# ESP32SSMB_V1_2.net
KiCad netlist of a schematic drawn in Altium Designer
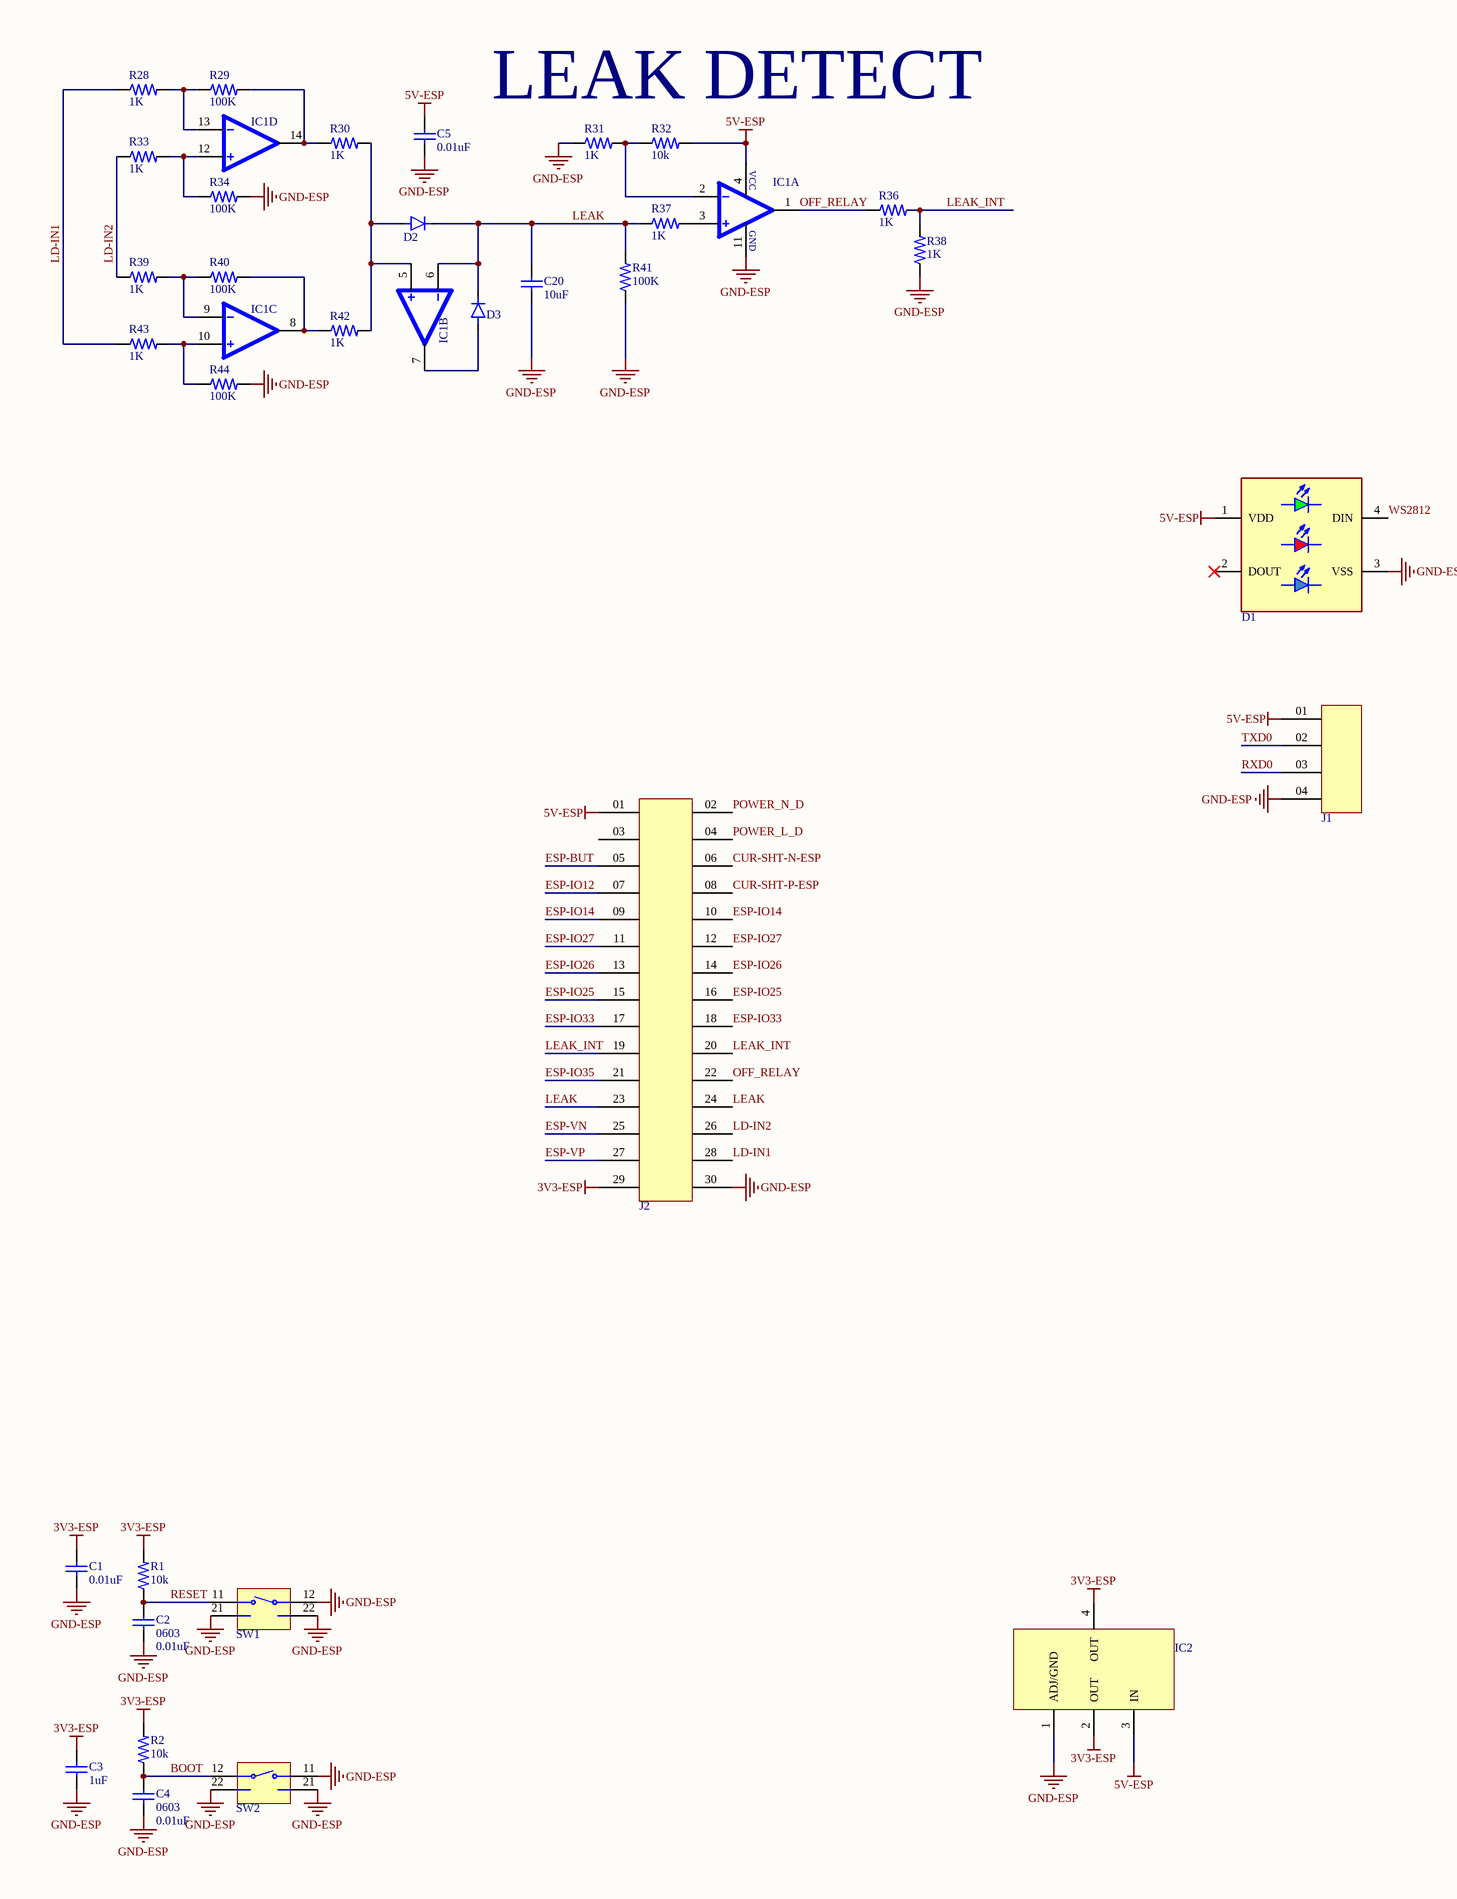
[diagram p0: ESP32SSMB V1.2 .SchDoc, left]
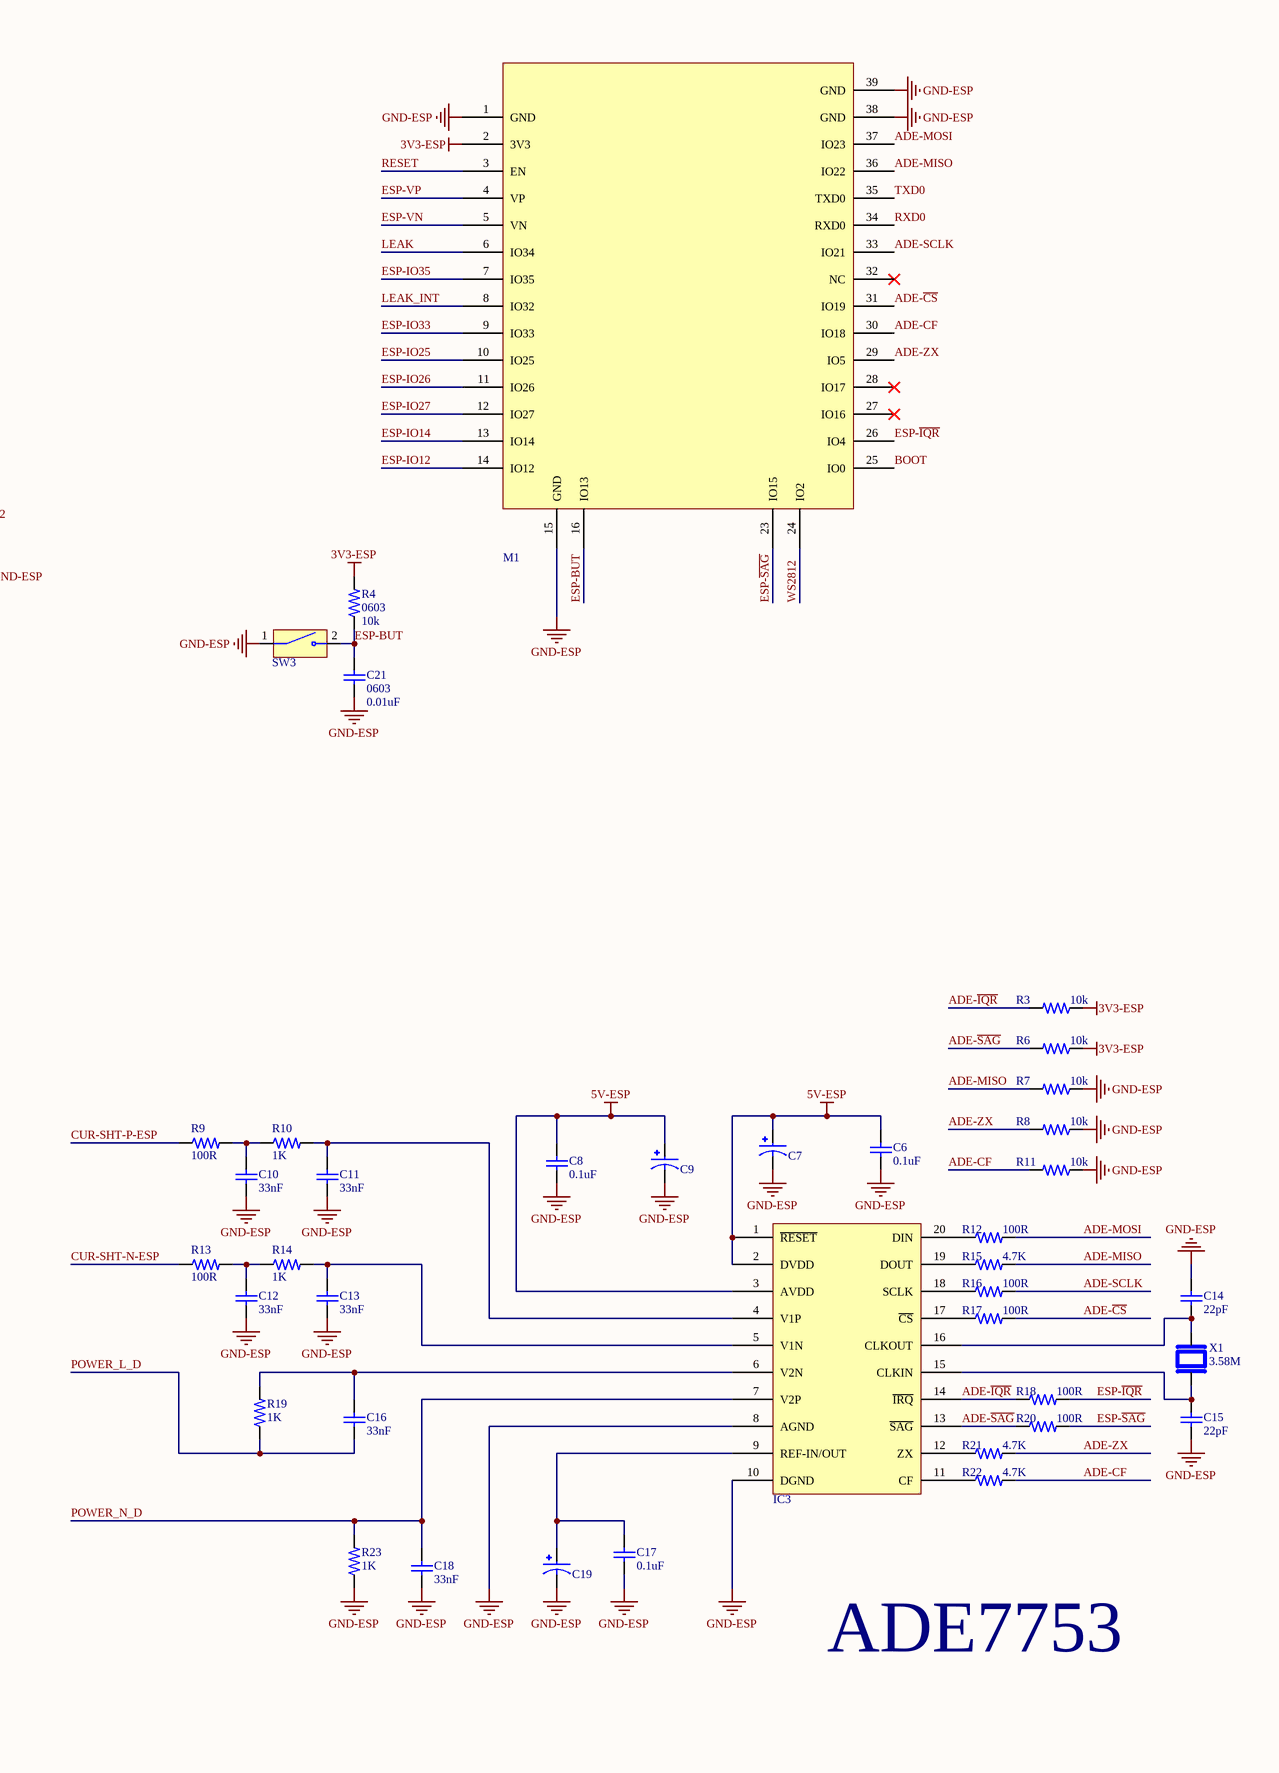
[diagram p1: ESP32SSMB V1.2 .SchDoc, right]

(export (version "E")
  (design (tool "Eeschema 10.0.6"))
  (components
    (comp (ref "C1")
      (value "0.01uF")
      (footprint "SMD-CAP-0603-YAGEO")
      (description "Multilayer Ceramic Capacitor, 0.1 uF, 10 V, ± 10%, X7R, 0603 [1608 Metric]")
      (fields
        (field (name "MANUFACTURER") "Yageo")
        (field (name "MANUFACTURER PART NUMBER") "CC0603KRX7R6BB104")
        (field (name "DESIGNER") "TVBac")
      )
      (libsource (lib "Capacitors") (part "CAP; 0.1uF; 10V; 0603; SMD; CC0603KRX7R6BB104"))
    )
    (comp (ref "C2")
      (value "0.01uF")
      (footprint "SMD-CAP-0603-YAGEO")
      (description "Multilayer Ceramic Capacitor, 0.01 uF, 16 V, ± 10%, X7R, 0603 [1608 Metric]")
      (fields
        (field (name "MANUFACTURER") "Yageo")
        (field (name "MANUFACTURER PART NUMBER") "CC0603KRX7R7BB103")
        (field (name "PACKAGE") "0603")
        (field (name "DESIGNER") "TVBac")
      )
      (libsource (lib "Capacitors") (part "CAP; 0.01uF; 16V; 0603; SMD; CC0603KRX7R7BB103"))
    )
    (comp (ref "C3")
      (value "1uF")
      (footprint "SMD-CAP-0603-YAGEO")
      (description "0603 1 uF 16 V ±10 % Tolerance X7R SMT Multilayer Ceramic Capacitor")
      (fields
        (field (name "MANUFACTURER") "Yageo")
        (field (name "MANUFACTURER PART NUMBER") "CC0603KRX7R7BB105")
        (field (name "DESIGNER") "TVBac")
      )
      (libsource (lib "Capacitors") (part "CAP; 1uF; 16V; 0603; SMD; CC0603KRX7R7BB105"))
    )
    (comp (ref "C4")
      (value "0.01uF")
      (footprint "SMD-CAP-0603-YAGEO")
      (description "Multilayer Ceramic Capacitor, 0.01 uF, 16 V, ± 10%, X7R, 0603 [1608 Metric]")
      (fields
        (field (name "MANUFACTURER") "Yageo")
        (field (name "MANUFACTURER PART NUMBER") "CC0603KRX7R7BB103")
        (field (name "PACKAGE") "0603")
        (field (name "DESIGNER") "TVBac")
      )
      (libsource (lib "Capacitors") (part "CAP; 0.01uF; 16V; 0603; SMD; CC0603KRX7R7BB103"))
    )
    (comp (ref "C5")
      (value "0.01uF")
      (footprint "SMD-CAP-0603-YAGEO")
      (description "Multilayer Ceramic Capacitor, 0.1 uF, 10 V, ± 10%, X7R, 0603 [1608 Metric]")
      (fields
        (field (name "MANUFACTURER") "Yageo")
        (field (name "MANUFACTURER PART NUMBER") "CC0603KRX7R6BB104")
        (field (name "DESIGNER") "TVBac")
      )
      (libsource (lib "Capacitors") (part "CAP; 0.1uF; 10V; 0603; SMD; CC0603KRX7R6BB104"))
    )
    (comp (ref "C6")
      (value "0.1uF")
      (footprint "SMD-CAP-0603-YAGEO")
      (description "0603 0.1 uF 16 V ±10 % Tolerance X7R SMT Multilayer Ceramic Capacitor")
      (fields
        (field (name "MANUFACTURER") "Yageo")
        (field (name "MANUFACTURER PART NUMBER") "CC0603KRX7R7BB104")
        (field (name "DESIGNER") "TVBac")
      )
      (libsource (lib "Capacitors") (part "CAP; 0.1uF; 16V; 0603; SMD; CC0603KRX7R7BB104"))
    )
    (comp (ref "C7")
      (value "10 µF Molded Tantalum Capacitors 10 V 1206 (3216 Metric) 3.8Ohm")
      (footprint "SMD-CAP-TAN-1206-KEMET")
      (description "Capacitor, Tantalum, Solid, Polarized, 10 V, 10 Uf, Surface Mount, 1206, Lead Free")
      (fields
        (field (name "MANUFACTURER") "KEMET")
        (field (name "MANUFACTURER PART NUMBER") "T491A106M010AT")
        (field (name "DESIGNER") "TVBac")
      )
      (libsource (lib "Capacitors") (part "CAP; CAP_TAN; 10uF; 10V; T491A106M010AT"))
    )
    (comp (ref "C8")
      (value "0.1uF")
      (footprint "SMD-CAP-0603-YAGEO")
      (description "0603 0.1 uF 16 V ±10 % Tolerance X7R SMT Multilayer Ceramic Capacitor")
      (fields
        (field (name "MANUFACTURER") "Yageo")
        (field (name "MANUFACTURER PART NUMBER") "CC0603KRX7R7BB104")
        (field (name "DESIGNER") "TVBac")
      )
      (libsource (lib "Capacitors") (part "CAP; 0.1uF; 16V; 0603; SMD; CC0603KRX7R7BB104"))
    )
    (comp (ref "C9")
      (value "10 µF Molded Tantalum Capacitors 10 V 1206 (3216 Metric) 3.8Ohm")
      (footprint "SMD-CAP-TAN-1206-KEMET")
      (description "Capacitor, Tantalum, Solid, Polarized, 10 V, 10 Uf, Surface Mount, 1206, Lead Free")
      (fields
        (field (name "MANUFACTURER") "KEMET")
        (field (name "MANUFACTURER PART NUMBER") "T491A106M010AT")
        (field (name "DESIGNER") "TVBac")
      )
      (libsource (lib "Capacitors") (part "CAP; CAP_TAN; 10uF; 10V; T491A106M010AT"))
    )
    (comp (ref "C10")
      (value "33nF")
      (footprint "SMD-CAP-0603-KEMET")
      (description "Multilayer Ceramic Capacitors MLCC - SMD/SMT 16V 0.033uF X7R 0603 5%")
      (fields
        (field (name "MANUFACTURER") "KEMET")
        (field (name "MANUFACTURER PART NUMBER") "C0603C333J4REC7411")
        (field (name "DESIGNER") "TVBac")
      )
      (libsource (lib "Capacitors") (part "CAP; 0.033uF; 33nF; 0603; 16V; C0603C333J4REC7411"))
    )
    (comp (ref "C11")
      (value "33nF")
      (footprint "SMD-CAP-0603-KEMET")
      (description "Multilayer Ceramic Capacitors MLCC - SMD/SMT 16V 0.033uF X7R 0603 5%")
      (fields
        (field (name "MANUFACTURER") "KEMET")
        (field (name "MANUFACTURER PART NUMBER") "C0603C333J4REC7411")
        (field (name "DESIGNER") "TVBac")
      )
      (libsource (lib "Capacitors") (part "CAP; 0.033uF; 33nF; 0603; 16V; C0603C333J4REC7411"))
    )
    (comp (ref "C12")
      (value "33nF")
      (footprint "SMD-CAP-0603-KEMET")
      (description "Multilayer Ceramic Capacitors MLCC - SMD/SMT 16V 0.033uF X7R 0603 5%")
      (fields
        (field (name "MANUFACTURER") "KEMET")
        (field (name "MANUFACTURER PART NUMBER") "C0603C333J4REC7411")
        (field (name "DESIGNER") "TVBac")
      )
      (libsource (lib "Capacitors") (part "CAP; 0.033uF; 33nF; 0603; 16V; C0603C333J4REC7411"))
    )
    (comp (ref "C13")
      (value "33nF")
      (footprint "SMD-CAP-0603-KEMET")
      (description "Multilayer Ceramic Capacitors MLCC - SMD/SMT 16V 0.033uF X7R 0603 5%")
      (fields
        (field (name "MANUFACTURER") "KEMET")
        (field (name "MANUFACTURER PART NUMBER") "C0603C333J4REC7411")
        (field (name "DESIGNER") "TVBac")
      )
      (libsource (lib "Capacitors") (part "CAP; 0.033uF; 33nF; 0603; 16V; C0603C333J4REC7411"))
    )
    (comp (ref "C14")
      (value "22pF")
      (footprint "SMD-CAP-0603-YAGEO")
      (description "Multilayer Ceramic Capacitor, 22 pF, 50 V, ï¿½ 1%, C0G (NP0), 0603 [1608 Metric]")
      (fields
        (field (name "MANUFACTURER") "Yageo")
        (field (name "MANUFACTURER PART NUMBER") "CC0603FRNPO9BN220")
        (field (name "DESIGNER") "TVBac")
      )
      (libsource (lib "Capacitors") (part "CAP; 22pF; 50V; SMD; CC0603FRNPO9BN220"))
    )
    (comp (ref "C15")
      (value "22pF")
      (footprint "SMD-CAP-0603-YAGEO")
      (description "Multilayer Ceramic Capacitor, 22 pF, 50 V, ï¿½ 1%, C0G (NP0), 0603 [1608 Metric]")
      (fields
        (field (name "MANUFACTURER") "Yageo")
        (field (name "MANUFACTURER PART NUMBER") "CC0603FRNPO9BN220")
        (field (name "DESIGNER") "TVBac")
      )
      (libsource (lib "Capacitors") (part "CAP; 22pF; 50V; SMD; CC0603FRNPO9BN220"))
    )
    (comp (ref "C16")
      (value "33nF")
      (footprint "SMD-CAP-0603-KEMET")
      (description "Multilayer Ceramic Capacitors MLCC - SMD/SMT 16V 0.033uF X7R 0603 5%")
      (fields
        (field (name "MANUFACTURER") "KEMET")
        (field (name "MANUFACTURER PART NUMBER") "C0603C333J4REC7411")
        (field (name "DESIGNER") "TVBac")
      )
      (libsource (lib "Capacitors") (part "CAP; 0.033uF; 33nF; 0603; 16V; C0603C333J4REC7411"))
    )
    (comp (ref "C17")
      (value "0.1uF")
      (footprint "SMD-CAP-0603-YAGEO")
      (description "0603 0.1 uF 16 V ±10 % Tolerance X7R SMT Multilayer Ceramic Capacitor")
      (fields
        (field (name "MANUFACTURER") "Yageo")
        (field (name "MANUFACTURER PART NUMBER") "CC0603KRX7R7BB104")
        (field (name "DESIGNER") "TVBac")
      )
      (libsource (lib "Capacitors") (part "CAP; 0.1uF; 16V; 0603; SMD; CC0603KRX7R7BB104"))
    )
    (comp (ref "C18")
      (value "33nF")
      (footprint "SMD-CAP-0603-KEMET")
      (description "Multilayer Ceramic Capacitors MLCC - SMD/SMT 16V 0.033uF X7R 0603 5%")
      (fields
        (field (name "MANUFACTURER") "KEMET")
        (field (name "MANUFACTURER PART NUMBER") "C0603C333J4REC7411")
        (field (name "DESIGNER") "TVBac")
      )
      (libsource (lib "Capacitors") (part "CAP; 0.033uF; 33nF; 0603; 16V; C0603C333J4REC7411"))
    )
    (comp (ref "C19")
      (value "10 µF Molded Tantalum Capacitors 10 V 1206 (3216 Metric) 3.8Ohm")
      (footprint "SMD-CAP-TAN-1206-KEMET")
      (description "Capacitor, Tantalum, Solid, Polarized, 10 V, 10 Uf, Surface Mount, 1206, Lead Free")
      (fields
        (field (name "MANUFACTURER") "KEMET")
        (field (name "MANUFACTURER PART NUMBER") "T491A106M010AT")
        (field (name "DESIGNER") "TVBac")
      )
      (libsource (lib "Capacitors") (part "CAP; CAP_TAN; 10uF; 10V; T491A106M010AT"))
    )
    (comp (ref "C20")
      (value "10uF")
      (footprint "SMD-CAP-0805-KEMET")
      (description "Multilayer Ceramic Capacitor, 10 uF, 6.3 V, ï¿½ 10%, X5R, 0805 [2012 Metric]")
      (fields
        (field (name "MANUFACTURER") "KEMET")
        (field (name "MANUFACTURER PART NUMBER") "C0805C106K9PACTU")
        (field (name "DESIGNER") "TVBac")
      )
      (libsource (lib "Capacitors") (part "CAP; 10uF; 10V; 0805; C0805C106K9PACTU"))
    )
    (comp (ref "C21")
      (value "0.01uF")
      (footprint "SMD-CAP-0603-YAGEO")
      (description "Multilayer Ceramic Capacitor, 0.01 uF, 16 V, ± 10%, X7R, 0603 [1608 Metric]")
      (fields
        (field (name "MANUFACTURER") "Yageo")
        (field (name "MANUFACTURER PART NUMBER") "CC0603KRX7R7BB103")
        (field (name "PACKAGE") "0603")
        (field (name "DESIGNER") "TVBac")
      )
      (libsource (lib "Capacitors") (part "CAP; 0.01uF; 16V; 0603; SMD; CC0603KRX7R7BB103"))
    )
    (comp (ref "D1")
      (value "Addressable Lighting - LED Serial NRZ (Shift Register) Red, Green, Blue (RGB) 5.00mm L x 5.00mm W")
      (footprint "SMD-LxW-5.0x5.0-WS2812-4PIN")
      (description "Address Led Red/grn/blue")
      (fields
        (field (name "MANUFACTURER") "SparkFun")
        (field (name "MANUFACTURER PART NUMBER") "COM-16347")
        (field (name "DESIGNER") "TVBac")
      )
      (libsource (lib "LED") (part "LED; RGB; WS2812; COM-16347"))
    )
    (comp (ref "D2")
      (value "Diode 1000 V 1A Surface Mount SOD-123FL")
      (footprint "SOD-123FL-SMCDS")
      (description "Diode Gen Purp 1KV 1A SOD123FL")
      (fields
        (field (name "MANUFACTURER") "Sangdest Microelectronics")
        (field (name "MANUFACTURER PART NUMBER") "1N4007FL")
        (field (name "DESIGNER") "TVBac")
      )
      (libsource (lib "Diode") (part "DIODE; SMD; 1N4007FLN4007;"))
    )
    (comp (ref "D3")
      (value "Diode 1000 V 1A Surface Mount SOD-123FL")
      (footprint "SOD-123FL-SMCDS")
      (description "Diode Gen Purp 1KV 1A SOD123FL")
      (fields
        (field (name "MANUFACTURER") "Sangdest Microelectronics")
        (field (name "MANUFACTURER PART NUMBER") "1N4007FL")
        (field (name "DESIGNER") "TVBac")
      )
      (libsource (lib "Diode") (part "DIODE; SMD; 1N4007FLN4007;"))
    )
    (comp (ref "IC1")
      (value "General Purpose Amplifier 4 Circuit 14-SOIC")
      (footprint "SOIC-14")
      (description "Quad 30-V 1.2-MHz operational amplifier 14-SOIC 0 to 70")
      (fields
        (field (name "MANUFACTURER") "Texas Instruments")
        (field (name "MANUFACTURER PART NUMBER") "LM324DR")
        (field (name "DESIGNER") "TVBac")
      )
      (libsource (lib "IC") (part "OPAM; SMD; LM324DR"))
    )
    (comp (ref "IC2")
      (value "Linear Voltage Regulator IC Positive Fixed 1 Output 1A SOT-223-3")
      (footprint "IC:SOT-223-3-DI")
      (description "Linear Voltage Regulator IC 1 Output 1A SOT-223")
      (fields
        (field (name "MF") "Diodes Inc.")
        (field (name "MP") "AZ1117EH-3.3TRG1")
        (field (name "DESIGNER") "TVBac")
      )
      (libsource (lib "IC") (part "LDO; 3V3; 1A; SMD; AZ1117EH-3.3TRG1"))
    )
    (comp (ref "IC3")
      (value "Single Phase Meter IC 20-SSOP")
      (footprint "SSOP-20-ADI")
      (description "Single Phase Multifunction Metering IC 20-Pin SSOP Tube")
      (fields
        (field (name "MANUFACTURER") "Analog Devices")
        (field (name "MANUFACTURER PART NUMBER") "ADE7753ARSZ")
        (field (name "DESIGNER") "TVBac")
      )
      (libsource (lib "IC") (part "ADE7753ARSZ"))
    )
    (comp (ref "J1")
      (value "Connector Header Through Hole 4 position 0.050\" (1.27mm)")
      (footprint "HEADER-1.27-4 - U3D")
      (description "Conn Unshrouded Header HDR 4 POS 1.27mm Solder ST Top Entry Thru-Hole Bulk")
      (fields
        (field (name "MANUFACTURER") "Samtec")
        (field (name "MANUFACTURER PART NUMBER") "TMS-104-02-G-S")
        (field (name "DESIGNER") "TVBac")
      )
      (libsource (lib "Socket") (part "HEADER; 4PIN; 1.27; VER; TMS-104-02-G-S"))
    )
    (comp (ref "J2")
      (value "HEADER; 15x2PIN; 2.54; HOR;")
      (footprint "HEADER-2.54-15x2-HOR")
      (fields (field (name "DESIGNER") "TVBac"))
      (libsource (lib "Socket") (part "HEADER; 15x2PIN; 2.54; HOR;"))
    )
    (comp (ref "M1")
      (value "Bluetooth, WiFi 802.11b/g/n, Bluetooth v4.2 +EDR, Class 1, 2 and 3 Transceiver Module 2.4GHz ~ 2.5GHz Integrated, Trace Surface Mount")
      (footprint "MODULE-ESP32-WROVER - WROOM")
      (description "Rf Txrx Module Bt Trace Ant SMD")
      (fields
        (field (name "MANUFACTURER") "Espressif Systems")
        (field (name "MANUFACTURER PART NUMBER") "ESP32-WROOM-32E-H4")
        (field (name "DESIGNER") "TVBac")
      )
      (libsource (lib "Modules") (part "ESP32-WROOM-WROVE-32E-H4; SMD;"))
    )
    (comp (ref "R1")
      (value "10k")
      (footprint "SMD-RES-0603-SEI")
      (description "SMD Chip Resistor, 10 kOhm, ± 1%, 250 mW, 0603 [1608 Metric], Thick Film, Anti-Surge")
      (fields
        (field (name "MANUFACTURER") "Rohm")
        (field (name "MANUFACTURER PART NUMBER") "ESR03EZPF1002")
        (field (name "DESIGNER") "TVBac")
      )
      (libsource (lib "Smartsocket") (part "RES; 10K; 0603; SMD; ESR03EZPF1002"))
    )
    (comp (ref "R2")
      (value "10k")
      (footprint "SMD-RES-0603-SEI")
      (description "SMD Chip Resistor, 10 kOhm, ± 1%, 250 mW, 0603 [1608 Metric], Thick Film, Anti-Surge")
      (fields
        (field (name "MANUFACTURER") "Rohm")
        (field (name "MANUFACTURER PART NUMBER") "ESR03EZPF1002")
        (field (name "DESIGNER") "TVBac")
      )
      (libsource (lib "Smartsocket") (part "RES; 10K; 0603; SMD; ESR03EZPF1002"))
    )
    (comp (ref "R3")
      (value "10k")
      (footprint "SMD-RES-0603-SEI")
      (description "SMD Chip Resistor, 10 kOhm, ± 1%, 250 mW, 0603 [1608 Metric], Thick Film, Anti-Surge")
      (fields
        (field (name "MANUFACTURER") "Rohm")
        (field (name "MANUFACTURER PART NUMBER") "ESR03EZPF1002")
        (field (name "DESIGNER") "TVBac")
      )
      (libsource (lib "Resistors") (part "RES; 10K; 0603; SMD; ESR03EZPF1002"))
    )
    (comp (ref "R4")
      (value "10k")
      (footprint "SMD-RES-0603-SEI")
      (description "SMD Chip Resistor, 10 kOhm, ± 1%, 250 mW, 0603 [1608 Metric], Thick Film, Anti-Surge")
      (fields
        (field (name "MANUFACTURER") "Rohm")
        (field (name "MANUFACTURER PART NUMBER") "ESR03EZPF1002")
        (field (name "PACKAGE") "0603")
        (field (name "DESIGNER") "TVBac")
      )
      (libsource (lib "Resistors") (part "RES; 10K; 0603; SMD; ESR03EZPF1002"))
    )
    (comp (ref "R6")
      (value "10k")
      (footprint "SMD-RES-0603-SEI")
      (description "SMD Chip Resistor, 10 kOhm, ± 1%, 250 mW, 0603 [1608 Metric], Thick Film, Anti-Surge")
      (fields
        (field (name "MANUFACTURER") "Rohm")
        (field (name "MANUFACTURER PART NUMBER") "ESR03EZPF1002")
        (field (name "DESIGNER") "TVBac")
      )
      (libsource (lib "Resistors") (part "RES; 10K; 0603; SMD; ESR03EZPF1002"))
    )
    (comp (ref "R7")
      (value "10k")
      (footprint "SMD-RES-0603-SEI")
      (description "SMD Chip Resistor, 10 kOhm, ± 1%, 250 mW, 0603 [1608 Metric], Thick Film, Anti-Surge")
      (fields
        (field (name "MANUFACTURER") "Rohm")
        (field (name "MANUFACTURER PART NUMBER") "ESR03EZPF1002")
        (field (name "DESIGNER") "TVBac")
      )
      (libsource (lib "Resistors") (part "RES; 10K; 0603; SMD; ESR03EZPF1002"))
    )
    (comp (ref "R8")
      (value "10k")
      (footprint "SMD-RES-0603-SEI")
      (description "SMD Chip Resistor, 10 kOhm, ± 1%, 250 mW, 0603 [1608 Metric], Thick Film, Anti-Surge")
      (fields
        (field (name "MANUFACTURER") "Rohm")
        (field (name "MANUFACTURER PART NUMBER") "ESR03EZPF1002")
        (field (name "DESIGNER") "TVBac")
      )
      (libsource (lib "Resistors") (part "RES; 10K; 0603; SMD; ESR03EZPF1002"))
    )
    (comp (ref "R9")
      (value "100R")
      (footprint "SMD-RES-0603-RS")
      (description "Res Thick Film 0603 100 Ohm 1% 0.1W(1/10W) ±100ppm/C Pad SMD T/R Automotive AEC-Q200")
      (fields
        (field (name "MANUFACTURER") "Rohm")
        (field (name "MANUFACTURER PART NUMBER") "KTR03EZPF1000")
        (field (name "DESIGNER") "TVBac")
      )
      (libsource (lib "Resistors") (part "RES; 100R; 0603; SMD; KTR03EZPF1000"))
    )
    (comp (ref "R10")
      (value "1K")
      (footprint "SMD-RES-0603-SEI")
      (description "SMD Chip Resistor, 1 kOhm, ± 1%, 250 mW, 0603 [1608 Metric], Thick Film, Anti-Surge")
      (fields
        (field (name "MANUFACTURER") "Rohm")
        (field (name "MANUFACTURER PART NUMBER") "ESR03EZPF1001")
        (field (name "DESIGNER") "TVBac")
      )
      (libsource (lib "Resistors") (part "RES; 1K; 0603; SMD; ESR03EZPF1001"))
    )
    (comp (ref "R11")
      (value "10k")
      (footprint "SMD-RES-0603-SEI")
      (description "SMD Chip Resistor, 10 kOhm, ± 1%, 250 mW, 0603 [1608 Metric], Thick Film, Anti-Surge")
      (fields
        (field (name "MANUFACTURER") "Rohm")
        (field (name "MANUFACTURER PART NUMBER") "ESR03EZPF1002")
        (field (name "DESIGNER") "TVBac")
      )
      (libsource (lib "Resistors") (part "RES; 10K; 0603; SMD; ESR03EZPF1002"))
    )
    (comp (ref "R12")
      (value "100R")
      (footprint "SMD-RES-0603-RS")
      (description "Res Thick Film 0603 100 Ohm 1% 0.1W(1/10W) ±100ppm/C Pad SMD T/R Automotive AEC-Q200")
      (fields
        (field (name "MANUFACTURER") "Rohm")
        (field (name "MANUFACTURER PART NUMBER") "KTR03EZPF1000")
        (field (name "DESIGNER") "TVBac")
      )
      (libsource (lib "Resistors") (part "RES; 100R; 0603; SMD; KTR03EZPF1000"))
    )
    (comp (ref "R13")
      (value "100R")
      (footprint "SMD-RES-0603-RS")
      (description "Res Thick Film 0603 100 Ohm 1% 0.1W(1/10W) ±100ppm/C Pad SMD T/R Automotive AEC-Q200")
      (fields
        (field (name "MANUFACTURER") "Rohm")
        (field (name "MANUFACTURER PART NUMBER") "KTR03EZPF1000")
        (field (name "DESIGNER") "TVBac")
      )
      (libsource (lib "Resistors") (part "RES; 100R; 0603; SMD; KTR03EZPF1000"))
    )
    (comp (ref "R14")
      (value "1K")
      (footprint "SMD-RES-0603-SEI")
      (description "SMD Chip Resistor, 1 kOhm, ± 1%, 250 mW, 0603 [1608 Metric], Thick Film, Anti-Surge")
      (fields
        (field (name "MANUFACTURER") "Rohm")
        (field (name "MANUFACTURER PART NUMBER") "ESR03EZPF1001")
        (field (name "DESIGNER") "TVBac")
      )
      (libsource (lib "Resistors") (part "RES; 1K; 0603; SMD; ESR03EZPF1001"))
    )
    (comp (ref "R15")
      (value "4.7K")
      (footprint "SMD-RES-0603-RS")
      (description "Res Anti-Sulfured Thick Film 0603 4.7k Ohm 1% 1/10W ±100ppm/°C Molded Paper T/R")
      (fields
        (field (name "MANUFACTURER") "Rohm")
        (field (name "MANUFACTURER PART NUMBER") "SFR03EZPF4701")
        (field (name "DESIGNER") "TVBac")
      )
      (libsource (lib "Resistors") (part "RES; 4.7K; 0603; SMD; SFR03EZPF4701"))
    )
    (comp (ref "R16")
      (value "100R")
      (footprint "SMD-RES-0603-RS")
      (description "Res Thick Film 0603 100 Ohm 1% 0.1W(1/10W) ±100ppm/C Pad SMD T/R Automotive AEC-Q200")
      (fields
        (field (name "MANUFACTURER") "Rohm")
        (field (name "MANUFACTURER PART NUMBER") "KTR03EZPF1000")
        (field (name "DESIGNER") "TVBac")
      )
      (libsource (lib "Resistors") (part "RES; 100R; 0603; SMD; KTR03EZPF1000"))
    )
    (comp (ref "R17")
      (value "100R")
      (footprint "SMD-RES-0603-RS")
      (description "Res Thick Film 0603 100 Ohm 1% 0.1W(1/10W) ±100ppm/C Pad SMD T/R Automotive AEC-Q200")
      (fields
        (field (name "MANUFACTURER") "Rohm")
        (field (name "MANUFACTURER PART NUMBER") "KTR03EZPF1000")
        (field (name "DESIGNER") "TVBac")
      )
      (libsource (lib "Resistors") (part "RES; 100R; 0603; SMD; KTR03EZPF1000"))
    )
    (comp (ref "R18")
      (value "100R")
      (footprint "SMD-RES-0603-RS")
      (description "Res Thick Film 0603 100 Ohm 1% 0.1W(1/10W) ±100ppm/C Pad SMD T/R Automotive AEC-Q200")
      (fields
        (field (name "MANUFACTURER") "Rohm")
        (field (name "MANUFACTURER PART NUMBER") "KTR03EZPF1000")
        (field (name "DESIGNER") "TVBac")
      )
      (libsource (lib "Resistors") (part "RES; 100R; 0603; SMD; KTR03EZPF1000"))
    )
    (comp (ref "R19")
      (value "1K")
      (footprint "SMD-RES-0603-SEI")
      (description "SMD Chip Resistor, 1 kOhm, ± 1%, 250 mW, 0603 [1608 Metric], Thick Film, Anti-Surge")
      (fields
        (field (name "MANUFACTURER") "Rohm")
        (field (name "MANUFACTURER PART NUMBER") "ESR03EZPF1001")
        (field (name "DESIGNER") "TVBac")
      )
      (libsource (lib "Resistors") (part "RES; 1K; 0603; SMD; ESR03EZPF1001"))
    )
    (comp (ref "R20")
      (value "100R")
      (footprint "SMD-RES-0603-RS")
      (description "Res Thick Film 0603 100 Ohm 1% 0.1W(1/10W) ±100ppm/C Pad SMD T/R Automotive AEC-Q200")
      (fields
        (field (name "MANUFACTURER") "Rohm")
        (field (name "MANUFACTURER PART NUMBER") "KTR03EZPF1000")
        (field (name "DESIGNER") "TVBac")
      )
      (libsource (lib "Resistors") (part "RES; 100R; 0603; SMD; KTR03EZPF1000"))
    )
    (comp (ref "R21")
      (value "4.7K")
      (footprint "SMD-RES-0603-RS")
      (description "Res Anti-Sulfured Thick Film 0603 4.7k Ohm 1% 1/10W ±100ppm/°C Molded Paper T/R")
      (fields
        (field (name "MANUFACTURER") "Rohm")
        (field (name "MANUFACTURER PART NUMBER") "SFR03EZPF4701")
        (field (name "DESIGNER") "TVBac")
      )
      (libsource (lib "Resistors") (part "RES; 4.7K; 0603; SMD; SFR03EZPF4701"))
    )
    (comp (ref "R22")
      (value "4.7K")
      (footprint "SMD-RES-0603-RS")
      (description "Res Anti-Sulfured Thick Film 0603 4.7k Ohm 1% 1/10W ±100ppm/°C Molded Paper T/R")
      (fields
        (field (name "MANUFACTURER") "Rohm")
        (field (name "MANUFACTURER PART NUMBER") "SFR03EZPF4701")
        (field (name "DESIGNER") "TVBac")
      )
      (libsource (lib "Resistors") (part "RES; 4.7K; 0603; SMD; SFR03EZPF4701"))
    )
    (comp (ref "R23")
      (value "1K")
      (footprint "SMD-RES-0603-SEI")
      (description "SMD Chip Resistor, 1 kOhm, ± 1%, 250 mW, 0603 [1608 Metric], Thick Film, Anti-Surge")
      (fields
        (field (name "MANUFACTURER") "Rohm")
        (field (name "MANUFACTURER PART NUMBER") "ESR03EZPF1001")
        (field (name "DESIGNER") "TVBac")
      )
      (libsource (lib "Resistors") (part "RES; 1K; 0603; SMD; ESR03EZPF1001"))
    )
    (comp (ref "R28")
      (value "1K")
      (footprint "SMD-RES-0603-SEI")
      (description "SMD Chip Resistor, 1 kOhm, ± 1%, 250 mW, 0603 [1608 Metric], Thick Film, Anti-Surge")
      (fields
        (field (name "MANUFACTURER") "Rohm")
        (field (name "MANUFACTURER PART NUMBER") "ESR03EZPF1001")
        (field (name "DESIGNER") "TVBac")
      )
      (libsource (lib "Resistors") (part "RES; 1K; 0603; SMD; ESR03EZPF1001"))
    )
    (comp (ref "R29")
      (value "100K")
      (footprint "SMD-RES-0603-SEI")
      (description "Res Thick Film 0603 100K Ohm 5% 0.25W(1/4W) ±200ppm/C Pad SMD Automotive T/R")
      (fields
        (field (name "MANUFACTURER") "Rohm")
        (field (name "MANUFACTURER PART NUMBER") "ESR03EZPJ104")
        (field (name "DESIGNER") "TVBac")
      )
      (libsource (lib "Resistors") (part "RES; 100K; 0603; SMD; ESR03EZPJ104"))
    )
    (comp (ref "R30")
      (value "1K")
      (footprint "SMD-RES-0603-SEI")
      (description "SMD Chip Resistor, 1 kOhm, ± 1%, 250 mW, 0603 [1608 Metric], Thick Film, Anti-Surge")
      (fields
        (field (name "MANUFACTURER") "Rohm")
        (field (name "MANUFACTURER PART NUMBER") "ESR03EZPF1001")
        (field (name "DESIGNER") "TVBac")
      )
      (libsource (lib "Resistors") (part "RES; 1K; 0603; SMD; ESR03EZPF1001"))
    )
    (comp (ref "R31")
      (value "1K")
      (footprint "SMD-RES-0603-SEI")
      (description "SMD Chip Resistor, 1 kOhm, ± 1%, 250 mW, 0603 [1608 Metric], Thick Film, Anti-Surge")
      (fields
        (field (name "MANUFACTURER") "Rohm")
        (field (name "MANUFACTURER PART NUMBER") "ESR03EZPF1001")
        (field (name "DESIGNER") "TVBac")
      )
      (libsource (lib "Resistors") (part "RES; 1K; 0603; SMD; ESR03EZPF1001"))
    )
    (comp (ref "R32")
      (value "10k")
      (footprint "SMD-RES-0603-SEI")
      (description "SMD Chip Resistor, 10 kOhm, ± 1%, 250 mW, 0603 [1608 Metric], Thick Film, Anti-Surge")
      (fields
        (field (name "MANUFACTURER") "Rohm")
        (field (name "MANUFACTURER PART NUMBER") "ESR03EZPF1002")
        (field (name "DESIGNER") "TVBac")
      )
      (libsource (lib "Resistors") (part "RES; 10K; 0603; SMD; ESR03EZPF1002"))
    )
    (comp (ref "R33")
      (value "1K")
      (footprint "SMD-RES-0603-SEI")
      (description "SMD Chip Resistor, 1 kOhm, ± 1%, 250 mW, 0603 [1608 Metric], Thick Film, Anti-Surge")
      (fields
        (field (name "MANUFACTURER") "Rohm")
        (field (name "MANUFACTURER PART NUMBER") "ESR03EZPF1001")
        (field (name "DESIGNER") "TVBac")
      )
      (libsource (lib "Resistors") (part "RES; 1K; 0603; SMD; ESR03EZPF1001"))
    )
    (comp (ref "R34")
      (value "100K")
      (footprint "SMD-RES-0603-SEI")
      (description "Res Thick Film 0603 100K Ohm 5% 0.25W(1/4W) ±200ppm/C Pad SMD Automotive T/R")
      (fields
        (field (name "MANUFACTURER") "Rohm")
        (field (name "MANUFACTURER PART NUMBER") "ESR03EZPJ104")
        (field (name "DESIGNER") "TVBac")
      )
      (libsource (lib "Resistors") (part "RES; 100K; 0603; SMD; ESR03EZPJ104"))
    )
    (comp (ref "R36")
      (value "1K")
      (footprint "SMD-RES-0603-SEI")
      (description "SMD Chip Resistor, 1 kOhm, ± 1%, 250 mW, 0603 [1608 Metric], Thick Film, Anti-Surge")
      (fields
        (field (name "MANUFACTURER") "Rohm")
        (field (name "MANUFACTURER PART NUMBER") "ESR03EZPF1001")
        (field (name "DESIGNER") "TVBac")
      )
      (libsource (lib "Resistors") (part "RES; 1K; 0603; SMD; ESR03EZPF1001"))
    )
    (comp (ref "R37")
      (value "1K")
      (footprint "SMD-RES-0603-SEI")
      (description "SMD Chip Resistor, 1 kOhm, ± 1%, 250 mW, 0603 [1608 Metric], Thick Film, Anti-Surge")
      (fields
        (field (name "MANUFACTURER") "Rohm")
        (field (name "MANUFACTURER PART NUMBER") "ESR03EZPF1001")
        (field (name "DESIGNER") "TVBac")
      )
      (libsource (lib "Resistors") (part "RES; 1K; 0603; SMD; ESR03EZPF1001"))
    )
    (comp (ref "R38")
      (value "1K")
      (footprint "SMD-RES-0603-SEI")
      (description "SMD Chip Resistor, 1 kOhm, ± 1%, 250 mW, 0603 [1608 Metric], Thick Film, Anti-Surge")
      (fields
        (field (name "MANUFACTURER") "Rohm")
        (field (name "MANUFACTURER PART NUMBER") "ESR03EZPF1001")
        (field (name "DESIGNER") "TVBac")
      )
      (libsource (lib "Resistors") (part "RES; 1K; 0603; SMD; ESR03EZPF1001"))
    )
    (comp (ref "R39")
      (value "1K")
      (footprint "SMD-RES-0603-SEI")
      (description "SMD Chip Resistor, 1 kOhm, ± 1%, 250 mW, 0603 [1608 Metric], Thick Film, Anti-Surge")
      (fields
        (field (name "MANUFACTURER") "Rohm")
        (field (name "MANUFACTURER PART NUMBER") "ESR03EZPF1001")
        (field (name "DESIGNER") "TVBac")
      )
      (libsource (lib "Resistors") (part "RES; 1K; 0603; SMD; ESR03EZPF1001"))
    )
    (comp (ref "R40")
      (value "100K")
      (footprint "SMD-RES-0603-SEI")
      (description "Res Thick Film 0603 100K Ohm 5% 0.25W(1/4W) ±200ppm/C Pad SMD Automotive T/R")
      (fields
        (field (name "MANUFACTURER") "Rohm")
        (field (name "MANUFACTURER PART NUMBER") "ESR03EZPJ104")
        (field (name "DESIGNER") "TVBac")
      )
      (libsource (lib "Resistors") (part "RES; 100K; 0603; SMD; ESR03EZPJ104"))
    )
    (comp (ref "R41")
      (value "100K")
      (footprint "SMD-RES-0603-SEI")
      (description "Res Thick Film 0603 100K Ohm 5% 0.25W(1/4W) ±200ppm/C Pad SMD Automotive T/R")
      (fields
        (field (name "MANUFACTURER") "Rohm")
        (field (name "MANUFACTURER PART NUMBER") "ESR03EZPJ104")
        (field (name "DESIGNER") "TVBac")
      )
      (libsource (lib "Resistors") (part "RES; 100K; 0603; SMD; ESR03EZPJ104"))
    )
    (comp (ref "R42")
      (value "1K")
      (footprint "SMD-RES-0603-SEI")
      (description "SMD Chip Resistor, 1 kOhm, ± 1%, 250 mW, 0603 [1608 Metric], Thick Film, Anti-Surge")
      (fields
        (field (name "MANUFACTURER") "Rohm")
        (field (name "MANUFACTURER PART NUMBER") "ESR03EZPF1001")
        (field (name "DESIGNER") "TVBac")
      )
      (libsource (lib "Resistors") (part "RES; 1K; 0603; SMD; ESR03EZPF1001"))
    )
    (comp (ref "R43")
      (value "1K")
      (footprint "SMD-RES-0603-SEI")
      (description "SMD Chip Resistor, 1 kOhm, ± 1%, 250 mW, 0603 [1608 Metric], Thick Film, Anti-Surge")
      (fields
        (field (name "MANUFACTURER") "Rohm")
        (field (name "MANUFACTURER PART NUMBER") "ESR03EZPF1001")
        (field (name "DESIGNER") "TVBac")
      )
      (libsource (lib "Resistors") (part "RES; 1K; 0603; SMD; ESR03EZPF1001"))
    )
    (comp (ref "R44")
      (value "100K")
      (footprint "SMD-RES-0603-SEI")
      (description "Res Thick Film 0603 100K Ohm 5% 0.25W(1/4W) ±200ppm/C Pad SMD Automotive T/R")
      (fields
        (field (name "MANUFACTURER") "Rohm")
        (field (name "MANUFACTURER PART NUMBER") "ESR03EZPJ104")
        (field (name "DESIGNER") "TVBac")
      )
      (libsource (lib "Resistors") (part "RES; 100K; 0603; SMD; ESR03EZPJ104"))
    )
    (comp (ref "SW1")
      (value "https://www.digikey.com/en/products/detail/panasonic-electronic-components/EVQ-P7L01P/4429453")
      (footprint "SW-HxLxW-1.1x3.5x2.9-PEC")
      (description "Tactile Switch SPST-NO Side Actuated Surface Mount, Right Angle")
      (fields (field (name "MP") "EVQ-P7L01P") (field (name "MF") "Panasonic Electronic Components"))
      (libsource (lib "Button") (part "BUT; SW; SMD; EVQ-P7L01P"))
    )
    (comp (ref "SW2")
      (value "https://www.digikey.com/en/products/detail/panasonic-electronic-components/EVQ-P7L01P/4429453")
      (footprint "SW-HxLxW-1.1x3.5x2.9-PEC")
      (description "Tactile Switch SPST-NO Side Actuated Surface Mount, Right Angle")
      (fields (field (name "MP") "EVQ-P7L01P") (field (name "MF") "Panasonic Electronic Components"))
      (libsource (lib "") (part "BUT; SW; SMD; EVQ-P7L01P_1"))
    )
    (comp (ref "SW3")
      (value "Tactile Switch SPST-NO Top Actuated Surface Mount")
      (footprint "SW-HxLxW-5.0x6.0x3.5-C&K")
      (description "Switch Tactile N.O. SPST Rectangular Button J-Bend 0.05A 12VDC 1.77N SMD T/R")
      (fields
        (field (name "MANUFACTURER") "ITT C&K")
        (field (name "MANUFACTURER PART NUMBER") "PTS636SM50JSMTRLFS")
      )
      (libsource (lib "Button") (part "BUT; SW; SMD; PTS636SM50JSMTRLFS"))
    )
    (comp (ref "X1")
      (value "3.58M")
      (footprint "SMD-HC-49/US-ALLC")
      (description "Crystal 3.579545MHz ±20ppm (Tol) ±50ppm (Stability) 18pF FUND 180Ohm 2-Pin HC-49/US SMD T/R")
      (fields
        (field (name "MANUFACTURER") "Abracon")
        (field (name "MANUFACTURER PART NUMBER") "ABLS-3.579545MHZ-B2-T")
        (field (name "DESIGNER") "TVBac")
      )
      (libsource (lib "Oscillators") (part "OSC; 3.58M; 3.579545M; ABLS-3.579545MHZ-B2-T"))
    )
  )
  (nets
    (net (code "1") (name "/ADE-CF") (class "Default")
      (node (ref "M1") (pin "30") (pinfunction "IO18_30") (pintype "passive"))
      (node (ref "R11") (pin "2") (pinfunction "2_2") (pintype "passive"))
      (node (ref "R22") (pin "2") (pinfunction "2_2") (pintype "passive"))
    )
    (net (code "2") (name "/ADE-MISO") (class "Default")
      (node (ref "M1") (pin "36") (pinfunction "IO22_36") (pintype "passive"))
      (node (ref "R15") (pin "2") (pinfunction "2_2") (pintype "passive"))
      (node (ref "R7") (pin "2") (pinfunction "2_2") (pintype "passive"))
    )
    (net (code "3") (name "/ADE-MOSI") (class "Default")
      (node (ref "M1") (pin "37") (pinfunction "IO23_37") (pintype "passive"))
      (node (ref "R12") (pin "2") (pinfunction "2_2") (pintype "passive"))
    )
    (net (code "4") (name "/ADE-SCLK") (class "Default")
      (node (ref "M1") (pin "33") (pinfunction "IO21_33") (pintype "passive"))
      (node (ref "R16") (pin "2") (pinfunction "2_2") (pintype "passive"))
    )
    (net (code "5") (name "/ADE-ZX") (class "Default")
      (node (ref "M1") (pin "29") (pinfunction "IO5_29") (pintype "passive"))
      (node (ref "R21") (pin "2") (pinfunction "2_2") (pintype "passive"))
      (node (ref "R8") (pin "2") (pinfunction "2_2") (pintype "passive"))
    )
    (net (code "6") (name "/ADE-~{CS}") (class "Default")
      (node (ref "M1") (pin "31") (pinfunction "IO19_31") (pintype "passive"))
      (node (ref "R17") (pin "2") (pinfunction "2_2") (pintype "passive"))
    )
    (net (code "7") (name "/ADE-~{IQR}") (class "Default")
      (node (ref "IC3") (pin "14") (pinfunction "~{IRQ}_14") (pintype "passive"))
      (node (ref "R18") (pin "1") (pinfunction "1_1") (pintype "passive"))
      (node (ref "R3") (pin "2") (pinfunction "2_2") (pintype "passive"))
    )
    (net (code "8") (name "/ADE-~{SAG}") (class "Default")
      (node (ref "IC3") (pin "13") (pinfunction "~{SAG}_13") (pintype "passive"))
      (node (ref "R20") (pin "1") (pinfunction "1_1") (pintype "passive"))
      (node (ref "R6") (pin "2") (pinfunction "2_2") (pintype "passive"))
    )
    (net (code "9") (name "/BOOT") (class "Default")
      (node (ref "C4") (pin "2") (pinfunction "2_2") (pintype "passive"))
      (node (ref "M1") (pin "25") (pinfunction "IO0_25") (pintype "passive"))
      (node (ref "R2") (pin "1") (pinfunction "1_1") (pintype "passive"))
      (node (ref "SW2") (pin "12") (pinfunction "2_12") (pintype "passive"))
    )
    (net (code "10") (name "/CUR-SHT-N-ESP") (class "Default")
      (node (ref "J2") (pin "06") (pinfunction "06_06") (pintype "passive"))
      (node (ref "R13") (pin "1") (pinfunction "1_1") (pintype "passive"))
    )
    (net (code "11") (name "/CUR-SHT-P-ESP") (class "Default")
      (node (ref "J2") (pin "08") (pinfunction "08_08") (pintype "passive"))
      (node (ref "R9") (pin "1") (pinfunction "1_1") (pintype "passive"))
    )
    (net (code "12") (name "/ESP-BUT") (class "Default")
      (node (ref "C21") (pin "2") (pinfunction "2_2") (pintype "passive"))
      (node (ref "J2") (pin "05") (pinfunction "05_05") (pintype "passive"))
      (node (ref "M1") (pin "16") (pinfunction "IO13_16") (pintype "passive"))
      (node (ref "R4") (pin "1") (pinfunction "1_1") (pintype "passive"))
      (node (ref "SW3") (pin "2") (pinfunction "NO_2") (pintype "passive"))
    )
    (net (code "13") (name "/ESP-IO12") (class "Default")
      (node (ref "J2") (pin "07") (pinfunction "07_07") (pintype "passive"))
      (node (ref "M1") (pin "14") (pinfunction "IO12_14") (pintype "passive"))
    )
    (net (code "14") (name "/ESP-IO14") (class "Default")
      (node (ref "J2") (pin "09") (pinfunction "09_09") (pintype "passive"))
      (node (ref "J2") (pin "10") (pinfunction "10_10") (pintype "passive"))
      (node (ref "M1") (pin "13") (pinfunction "IO14_13") (pintype "passive"))
    )
    (net (code "15") (name "/ESP-IO25") (class "Default")
      (node (ref "J2") (pin "15") (pinfunction "15_15") (pintype "passive"))
      (node (ref "J2") (pin "16") (pinfunction "16_16") (pintype "passive"))
      (node (ref "M1") (pin "10") (pinfunction "IO25_10") (pintype "passive"))
    )
    (net (code "16") (name "/ESP-IO26") (class "Default")
      (node (ref "J2") (pin "13") (pinfunction "13_13") (pintype "passive"))
      (node (ref "J2") (pin "14") (pinfunction "14_14") (pintype "passive"))
      (node (ref "M1") (pin "11") (pinfunction "IO26_11") (pintype "passive"))
    )
    (net (code "17") (name "/ESP-IO27") (class "Default")
      (node (ref "J2") (pin "11") (pinfunction "11_11") (pintype "passive"))
      (node (ref "J2") (pin "12") (pinfunction "12_12") (pintype "passive"))
      (node (ref "M1") (pin "12") (pinfunction "IO27_12") (pintype "passive"))
    )
    (net (code "18") (name "/ESP-IO33") (class "Default")
      (node (ref "J2") (pin "17") (pinfunction "17_17") (pintype "passive"))
      (node (ref "J2") (pin "18") (pinfunction "18_18") (pintype "passive"))
      (node (ref "M1") (pin "9") (pinfunction "IO33_9") (pintype "passive"))
    )
    (net (code "19") (name "/ESP-IO35") (class "Default")
      (node (ref "J2") (pin "21") (pinfunction "21_21") (pintype "passive"))
      (node (ref "M1") (pin "7") (pinfunction "IO35_7") (pintype "passive"))
    )
    (net (code "20") (name "/ESP-VN") (class "Default")
      (node (ref "J2") (pin "25") (pinfunction "25_25") (pintype "passive"))
      (node (ref "M1") (pin "5") (pinfunction "VN_5") (pintype "passive"))
    )
    (net (code "21") (name "/ESP-VP") (class "Default")
      (node (ref "J2") (pin "27") (pinfunction "27_27") (pintype "passive"))
      (node (ref "M1") (pin "4") (pinfunction "VP_4") (pintype "passive"))
    )
    (net (code "22") (name "/ESP-~{IQR}") (class "Default")
      (node (ref "M1") (pin "26") (pinfunction "IO4_26") (pintype "passive"))
      (node (ref "R18") (pin "2") (pinfunction "2_2") (pintype "passive"))
    )
    (net (code "23") (name "/ESP-~{SAG}") (class "Default")
      (node (ref "M1") (pin "23") (pinfunction "IO15_23") (pintype "passive"))
      (node (ref "R20") (pin "2") (pinfunction "2_2") (pintype "passive"))
    )
    (net (code "24") (name "/LD-IN1") (class "Default")
      (node (ref "J2") (pin "28") (pinfunction "28_28") (pintype "passive"))
      (node (ref "R28") (pin "1") (pinfunction "1_1") (pintype "passive"))
      (node (ref "R43") (pin "1") (pinfunction "1_1") (pintype "passive"))
    )
    (net (code "25") (name "/LD-IN2") (class "Default")
      (node (ref "J2") (pin "26") (pinfunction "26_26") (pintype "passive"))
      (node (ref "R33") (pin "1") (pinfunction "1_1") (pintype "passive"))
      (node (ref "R39") (pin "1") (pinfunction "1_1") (pintype "passive"))
    )
    (net (code "26") (name "/LEAK") (class "Default")
      (node (ref "C20") (pin "2") (pinfunction "2_2") (pintype "passive"))
      (node (ref "D2") (pin "K") (pinfunction "K_K") (pintype "passive"))
      (node (ref "D3") (pin "K") (pinfunction "K_K") (pintype "passive"))
      (node (ref "IC1") (pin "6") (pinfunction "2IN-_6") (pintype "passive"))
      (node (ref "J2") (pin "23") (pinfunction "23_23") (pintype "passive"))
      (node (ref "J2") (pin "24") (pinfunction "24_24") (pintype "passive"))
      (node (ref "M1") (pin "6") (pinfunction "IO34_6") (pintype "passive"))
      (node (ref "R37") (pin "1") (pinfunction "1_1") (pintype "passive"))
      (node (ref "R41") (pin "2") (pinfunction "2_2") (pintype "passive"))
    )
    (net (code "27") (name "/LEAK_INT") (class "Default")
      (node (ref "J2") (pin "19") (pinfunction "19_19") (pintype "passive"))
      (node (ref "J2") (pin "20") (pinfunction "20_20") (pintype "passive"))
      (node (ref "M1") (pin "8") (pinfunction "IO32_8") (pintype "passive"))
      (node (ref "R36") (pin "2") (pinfunction "2_2") (pintype "passive"))
      (node (ref "R38") (pin "2") (pinfunction "2_2") (pintype "passive"))
    )
    (net (code "28") (name "/OFF_RELAY") (class "Default")
      (node (ref "IC1") (pin "1") (pinfunction "1OUT_1") (pintype "passive"))
      (node (ref "J2") (pin "22") (pinfunction "22_22") (pintype "passive"))
      (node (ref "R36") (pin "1") (pinfunction "1_1") (pintype "passive"))
    )
    (net (code "29") (name "/POWER_L_D") (class "Default")
      (node (ref "C16") (pin "1") (pinfunction "1_1") (pintype "passive"))
      (node (ref "J2") (pin "04") (pinfunction "04_04") (pintype "passive"))
      (node (ref "R19") (pin "1") (pinfunction "1_1") (pintype "passive"))
    )
    (net (code "30") (name "/POWER_N_D") (class "Default")
      (node (ref "C18") (pin "2") (pinfunction "2_2") (pintype "passive"))
      (node (ref "IC3") (pin "7") (pinfunction "V2P_7") (pintype "passive"))
      (node (ref "J2") (pin "02") (pinfunction "02_02") (pintype "passive"))
      (node (ref "R23") (pin "2") (pinfunction "2_2") (pintype "passive"))
    )
    (net (code "31") (name "/RESET") (class "Default")
      (node (ref "C2") (pin "2") (pinfunction "2_2") (pintype "passive"))
      (node (ref "M1") (pin "3") (pinfunction "EN_3") (pintype "passive"))
      (node (ref "R1") (pin "1") (pinfunction "1_1") (pintype "passive"))
      (node (ref "SW1") (pin "11") (pinfunction "1_11") (pintype "passive"))
    )
    (net (code "32") (name "/RXD0") (class "Default")
      (node (ref "J1") (pin "03") (pinfunction "2_03") (pintype "passive"))
      (node (ref "M1") (pin "34") (pinfunction "RXD0_34") (pintype "passive"))
    )
    (net (code "33") (name "/TXD0") (class "Default")
      (node (ref "J1") (pin "02") (pinfunction "2_02") (pintype "passive"))
      (node (ref "M1") (pin "35") (pinfunction "TXD0_35") (pintype "passive"))
    )
    (net (code "34") (name "/WS2812") (class "Default")
      (node (ref "D1") (pin "4") (pinfunction "DIN_4") (pintype "passive"))
      (node (ref "M1") (pin "24") (pinfunction "IO2_24") (pintype "passive"))
    )
    (net (code "35") (name "3V3-ESP") (class "Default")
      (node (ref "C1") (pin "2") (pinfunction "2_2") (pintype "passive"))
      (node (ref "C3") (pin "2") (pinfunction "2_2") (pintype "passive"))
      (node (ref "IC2") (pin "2") (pinfunction "OUT_2") (pintype "passive"))
      (node (ref "IC2") (pin "4") (pinfunction "OUT_4") (pintype "passive"))
      (node (ref "J2") (pin "29") (pinfunction "29_29") (pintype "passive"))
      (node (ref "M1") (pin "2") (pinfunction "3V3_2") (pintype "passive"))
      (node (ref "R1") (pin "2") (pinfunction "2_2") (pintype "passive"))
      (node (ref "R2") (pin "2") (pinfunction "2_2") (pintype "passive"))
      (node (ref "R3") (pin "1") (pinfunction "1_1") (pintype "passive"))
      (node (ref "R4") (pin "2") (pinfunction "2_2") (pintype "passive"))
      (node (ref "R6") (pin "1") (pinfunction "1_1") (pintype "passive"))
    )
    (net (code "36") (name "5V-ESP") (class "Default")
      (node (ref "C5") (pin "2") (pinfunction "2_2") (pintype "passive"))
      (node (ref "C6") (pin "2") (pinfunction "2_2") (pintype "passive"))
      (node (ref "C7") (pin "1") (pinfunction "1_1") (pintype "passive"))
      (node (ref "C8") (pin "2") (pinfunction "2_2") (pintype "passive"))
      (node (ref "C9") (pin "1") (pinfunction "1_1") (pintype "passive"))
      (node (ref "D1") (pin "1") (pinfunction "VDD_1") (pintype "passive"))
      (node (ref "IC1") (pin "4") (pinfunction "VCC_4") (pintype "power_in"))
      (node (ref "IC2") (pin "3") (pinfunction "IN_3") (pintype "passive"))
      (node (ref "IC3") (pin "1") (pinfunction "~{RESET}_1") (pintype "passive"))
      (node (ref "IC3") (pin "2") (pinfunction "DVDD_2") (pintype "passive"))
      (node (ref "IC3") (pin "3") (pinfunction "AVDD_3") (pintype "passive"))
      (node (ref "J1") (pin "01") (pinfunction "1_01") (pintype "passive"))
      (node (ref "J2") (pin "01") (pinfunction "01_01") (pintype "passive"))
      (node (ref "R32") (pin "2") (pinfunction "2_2") (pintype "passive"))
    )
    (net (code "37") (name "GND-ESP") (class "Default")
      (node (ref "C1") (pin "1") (pinfunction "1_1") (pintype "passive"))
      (node (ref "C10") (pin "1") (pinfunction "1_1") (pintype "passive"))
      (node (ref "C11") (pin "1") (pinfunction "1_1") (pintype "passive"))
      (node (ref "C12") (pin "1") (pinfunction "1_1") (pintype "passive"))
      (node (ref "C13") (pin "1") (pinfunction "1_1") (pintype "passive"))
      (node (ref "C14") (pin "1") (pinfunction "1_1") (pintype "passive"))
      (node (ref "C15") (pin "2") (pinfunction "2_2") (pintype "passive"))
      (node (ref "C17") (pin "1") (pinfunction "1_1") (pintype "passive"))
      (node (ref "C18") (pin "1") (pinfunction "1_1") (pintype "passive"))
      (node (ref "C19") (pin "2") (pinfunction "2_2") (pintype "passive"))
      (node (ref "C2") (pin "1") (pinfunction "1_1") (pintype "passive"))
      (node (ref "C20") (pin "1") (pinfunction "1_1") (pintype "passive"))
      (node (ref "C21") (pin "1") (pinfunction "1_1") (pintype "passive"))
      (node (ref "C3") (pin "1") (pinfunction "1_1") (pintype "passive"))
      (node (ref "C4") (pin "1") (pinfunction "1_1") (pintype "passive"))
      (node (ref "C5") (pin "1") (pinfunction "1_1") (pintype "passive"))
      (node (ref "C6") (pin "1") (pinfunction "1_1") (pintype "passive"))
      (node (ref "C7") (pin "2") (pinfunction "2_2") (pintype "passive"))
      (node (ref "C8") (pin "1") (pinfunction "1_1") (pintype "passive"))
      (node (ref "C9") (pin "2") (pinfunction "2_2") (pintype "passive"))
      (node (ref "D1") (pin "3") (pinfunction "VSS_3") (pintype "passive"))
      (node (ref "IC1") (pin "11") (pinfunction "GND_11") (pintype "power_in"))
      (node (ref "IC2") (pin "1") (pinfunction "ADJ/GND_1") (pintype "passive"))
      (node (ref "IC3") (pin "10") (pinfunction "DGND_10") (pintype "passive"))
      (node (ref "IC3") (pin "8") (pinfunction "AGND_8") (pintype "passive"))
      (node (ref "J1") (pin "04") (pinfunction "4_04") (pintype "passive"))
      (node (ref "J2") (pin "30") (pinfunction "30_30") (pintype "passive"))
      (node (ref "M1") (pin "1") (pinfunction "GND_1") (pintype "passive"))
      (node (ref "M1") (pin "15") (pinfunction "GND_15") (pintype "passive"))
      (node (ref "M1") (pin "38") (pinfunction "GND_38") (pintype "passive"))
      (node (ref "M1") (pin "39") (pinfunction "GND_39") (pintype "passive"))
      (node (ref "R11") (pin "1") (pinfunction "1_1") (pintype "passive"))
      (node (ref "R23") (pin "1") (pinfunction "1_1") (pintype "passive"))
      (node (ref "R31") (pin "1") (pinfunction "1_1") (pintype "passive"))
      (node (ref "R34") (pin "2") (pinfunction "2_2") (pintype "passive"))
      (node (ref "R38") (pin "1") (pinfunction "1_1") (pintype "passive"))
      (node (ref "R41") (pin "1") (pinfunction "1_1") (pintype "passive"))
      (node (ref "R44") (pin "2") (pinfunction "2_2") (pintype "passive"))
      (node (ref "R7") (pin "1") (pinfunction "1_1") (pintype "passive"))
      (node (ref "R8") (pin "1") (pinfunction "1_1") (pintype "passive"))
      (node (ref "SW1") (pin "12") (pinfunction "2_12") (pintype "passive"))
      (node (ref "SW1") (pin "21") (pinfunction "1_21") (pintype "passive"))
      (node (ref "SW1") (pin "22") (pinfunction "2_22") (pintype "passive"))
      (node (ref "SW2") (pin "11") (pinfunction "1_11") (pintype "passive"))
      (node (ref "SW2") (pin "21") (pinfunction "1_21") (pintype "passive"))
      (node (ref "SW2") (pin "22") (pinfunction "2_22") (pintype "passive"))
      (node (ref "SW3") (pin "1") (pinfunction "COM_1") (pintype "passive"))
    )
    (net (code "38") (name "Net-(C10-Pad2)") (class "Default")
      (node (ref "C10") (pin "2") (pinfunction "2_2") (pintype "passive"))
      (node (ref "R10") (pin "1") (pinfunction "1_1") (pintype "passive"))
      (node (ref "R9") (pin "2") (pinfunction "2_2") (pintype "passive"))
    )
    (net (code "39") (name "Net-(C12-Pad2)") (class "Default")
      (node (ref "C12") (pin "2") (pinfunction "2_2") (pintype "passive"))
      (node (ref "R13") (pin "2") (pinfunction "2_2") (pintype "passive"))
      (node (ref "R14") (pin "1") (pinfunction "1_1") (pintype "passive"))
    )
    (net (code "40") (name "Net-(IC1A-1IN+)") (class "Default")
      (node (ref "IC1") (pin "3") (pinfunction "1IN+_3") (pintype "passive"))
      (node (ref "R37") (pin "2") (pinfunction "2_2") (pintype "passive"))
    )
    (net (code "41") (name "Net-(IC1A-1IN-)") (class "Default")
      (node (ref "IC1") (pin "2") (pinfunction "1IN-_2") (pintype "passive"))
      (node (ref "R31") (pin "2") (pinfunction "2_2") (pintype "passive"))
      (node (ref "R32") (pin "1") (pinfunction "1_1") (pintype "passive"))
    )
    (net (code "42") (name "Net-(IC1B-2IN+)") (class "Default")
      (node (ref "D2") (pin "A") (pinfunction "A_A") (pintype "passive"))
      (node (ref "IC1") (pin "5") (pinfunction "2IN+_5") (pintype "passive"))
      (node (ref "R30") (pin "2") (pinfunction "2_2") (pintype "passive"))
      (node (ref "R42") (pin "2") (pinfunction "2_2") (pintype "passive"))
    )
    (net (code "43") (name "Net-(IC1B-2OUT)") (class "Default")
      (node (ref "D3") (pin "A") (pinfunction "A_A") (pintype "passive"))
      (node (ref "IC1") (pin "7") (pinfunction "2OUT_7") (pintype "passive"))
    )
    (net (code "44") (name "Net-(IC1C-3IN+)") (class "Default")
      (node (ref "IC1") (pin "10") (pinfunction "3IN+_10") (pintype "passive"))
      (node (ref "R43") (pin "2") (pinfunction "2_2") (pintype "passive"))
      (node (ref "R44") (pin "1") (pinfunction "1_1") (pintype "passive"))
    )
    (net (code "45") (name "Net-(IC1C-3IN-)") (class "Default")
      (node (ref "IC1") (pin "9") (pinfunction "3IN-_9") (pintype "passive"))
      (node (ref "R39") (pin "2") (pinfunction "2_2") (pintype "passive"))
      (node (ref "R40") (pin "1") (pinfunction "1_1") (pintype "passive"))
    )
    (net (code "46") (name "Net-(IC1C-3OUT)") (class "Default")
      (node (ref "IC1") (pin "8") (pinfunction "3OUT_8") (pintype "passive"))
      (node (ref "R40") (pin "2") (pinfunction "2_2") (pintype "passive"))
      (node (ref "R42") (pin "1") (pinfunction "1_1") (pintype "passive"))
    )
    (net (code "47") (name "Net-(IC1D-4IN+)") (class "Default")
      (node (ref "IC1") (pin "12") (pinfunction "4IN+_12") (pintype "passive"))
      (node (ref "R33") (pin "2") (pinfunction "2_2") (pintype "passive"))
      (node (ref "R34") (pin "1") (pinfunction "1_1") (pintype "passive"))
    )
    (net (code "48") (name "Net-(IC1D-4IN-)") (class "Default")
      (node (ref "IC1") (pin "13") (pinfunction "4IN-_13") (pintype "passive"))
      (node (ref "R28") (pin "2") (pinfunction "2_2") (pintype "passive"))
      (node (ref "R29") (pin "1") (pinfunction "1_1") (pintype "passive"))
    )
    (net (code "49") (name "Net-(IC1D-4OUT)") (class "Default")
      (node (ref "IC1") (pin "14") (pinfunction "4OUT_14") (pintype "passive"))
      (node (ref "R29") (pin "2") (pinfunction "2_2") (pintype "passive"))
      (node (ref "R30") (pin "1") (pinfunction "1_1") (pintype "passive"))
    )
    (net (code "50") (name "Net-(IC3-CF)") (class "Default")
      (node (ref "IC3") (pin "11") (pinfunction "CF_11") (pintype "passive"))
      (node (ref "R22") (pin "1") (pinfunction "1_1") (pintype "passive"))
    )
    (net (code "51") (name "Net-(IC3-CLKIN)") (class "Default")
      (node (ref "C15") (pin "1") (pinfunction "1_1") (pintype "passive"))
      (node (ref "IC3") (pin "15") (pinfunction "CLKIN_15") (pintype "passive"))
      (node (ref "X1") (pin "2") (pinfunction "2_2") (pintype "passive"))
    )
    (net (code "52") (name "Net-(IC3-CLKOUT)") (class "Default")
      (node (ref "C14") (pin "2") (pinfunction "2_2") (pintype "passive"))
      (node (ref "IC3") (pin "16") (pinfunction "CLKOUT_16") (pintype "passive"))
      (node (ref "X1") (pin "1") (pinfunction "1_1") (pintype "passive"))
    )
    (net (code "53") (name "Net-(IC3-DIN)") (class "Default")
      (node (ref "IC3") (pin "20") (pinfunction "DIN_20") (pintype "passive"))
      (node (ref "R12") (pin "1") (pinfunction "1_1") (pintype "passive"))
    )
    (net (code "54") (name "Net-(IC3-DOUT)") (class "Default")
      (node (ref "IC3") (pin "19") (pinfunction "DOUT_19") (pintype "passive"))
      (node (ref "R15") (pin "1") (pinfunction "1_1") (pintype "passive"))
    )
    (net (code "55") (name "Net-(IC3-REF-IN{slash}OUT)") (class "Default")
      (node (ref "C17") (pin "2") (pinfunction "2_2") (pintype "passive"))
      (node (ref "C19") (pin "1") (pinfunction "1_1") (pintype "passive"))
      (node (ref "IC3") (pin "9") (pinfunction "REF-IN/OUT_9") (pintype "passive"))
    )
    (net (code "56") (name "Net-(IC3-SCLK)") (class "Default")
      (node (ref "IC3") (pin "18") (pinfunction "SCLK_18") (pintype "passive"))
      (node (ref "R16") (pin "1") (pinfunction "1_1") (pintype "passive"))
    )
    (net (code "57") (name "Net-(IC3-V1N)") (class "Default")
      (node (ref "C13") (pin "2") (pinfunction "2_2") (pintype "passive"))
      (node (ref "IC3") (pin "5") (pinfunction "V1N_5") (pintype "passive"))
      (node (ref "R14") (pin "2") (pinfunction "2_2") (pintype "passive"))
    )
    (net (code "58") (name "Net-(IC3-V1P)") (class "Default")
      (node (ref "C11") (pin "2") (pinfunction "2_2") (pintype "passive"))
      (node (ref "IC3") (pin "4") (pinfunction "V1P_4") (pintype "passive"))
      (node (ref "R10") (pin "2") (pinfunction "2_2") (pintype "passive"))
    )
    (net (code "59") (name "Net-(IC3-V2N)") (class "Default")
      (node (ref "C16") (pin "2") (pinfunction "2_2") (pintype "passive"))
      (node (ref "IC3") (pin "6") (pinfunction "V2N_6") (pintype "passive"))
      (node (ref "R19") (pin "2") (pinfunction "2_2") (pintype "passive"))
    )
    (net (code "60") (name "Net-(IC3-ZX)") (class "Default")
      (node (ref "IC3") (pin "12") (pinfunction "ZX_12") (pintype "passive"))
      (node (ref "R21") (pin "1") (pinfunction "1_1") (pintype "passive"))
    )
    (net (code "61") (name "Net-(IC3-~{CS})") (class "Default")
      (node (ref "IC3") (pin "17") (pinfunction "~{CS}_17") (pintype "passive"))
      (node (ref "R17") (pin "1") (pinfunction "1_1") (pintype "passive"))
    )
    (net (code "62") (name "unconnected-(D1-DOUT-Pad2)") (class "Default")
      (node (ref "D1") (pin "2") (pinfunction "DOUT_2") (pintype "passive+no_connect"))
    )
    (net (code "63") (name "unconnected-(J2-Pad03)") (class "Default")
      (node (ref "J2") (pin "03") (pinfunction "03_03") (pintype "passive"))
    )
    (net (code "64") (name "unconnected-(M1-IO16-Pad27)") (class "Default")
      (node (ref "M1") (pin "27") (pinfunction "IO16_27") (pintype "passive+no_connect"))
    )
    (net (code "65") (name "unconnected-(M1-IO17-Pad28)") (class "Default")
      (node (ref "M1") (pin "28") (pinfunction "IO17_28") (pintype "passive+no_connect"))
    )
    (net (code "66") (name "unconnected-(M1-NC-Pad32)") (class "Default")
      (node (ref "M1") (pin "32") (pinfunction "NC_32") (pintype "passive+no_connect"))
    )
  )
)
